# Sheet.net
KiCad netlist of a schematic drawn in Altium Designer
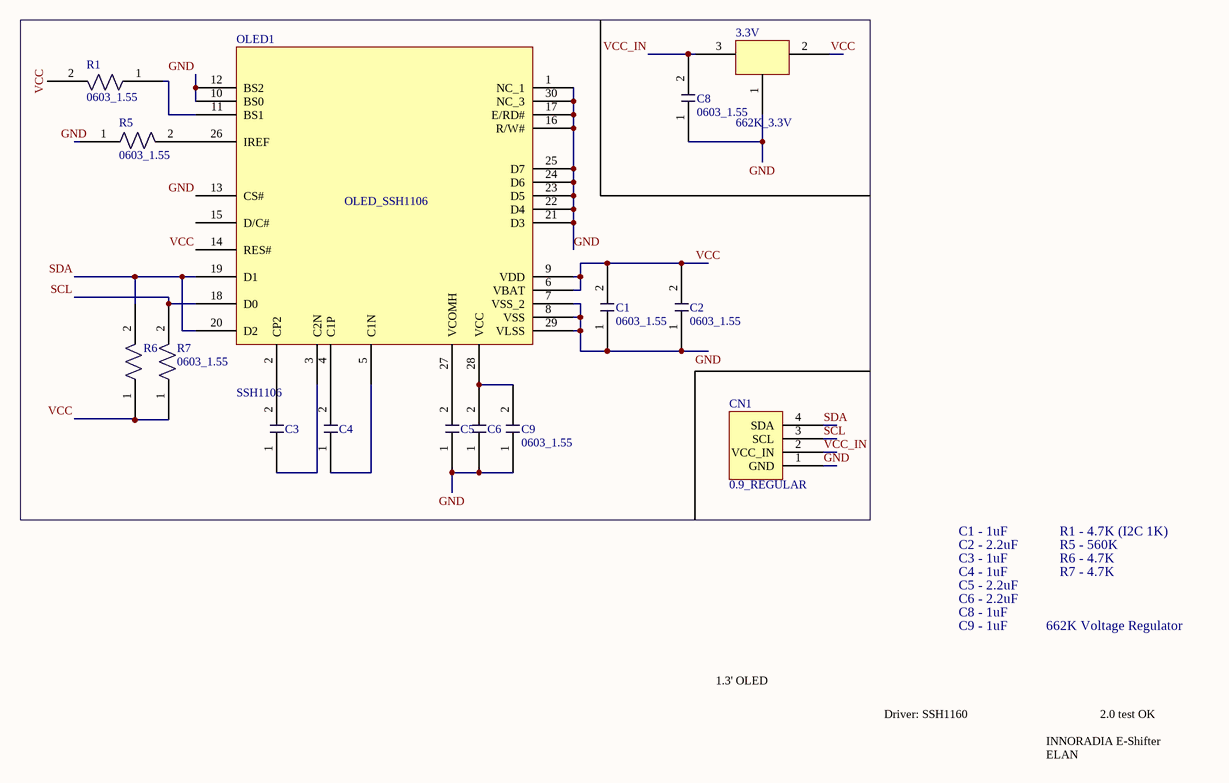
[diagram p0: Sheet.SchDoc]

(export (version "E")
  (design (tool "Eeschema 10.0.6"))
  (components
    (comp (ref "3.3V")
      (value "662K_3.3V")
      (footprint "662K_3.3V")
      (libsource (lib "Schlib") (part "662K_3.3V"))
    )
    (comp (ref "C1") (value "0603_1.55") (footprint "C_0603") (libsource (lib "Schlib") (part "C_0603")))
    (comp (ref "C2") (value "0603_1.55") (footprint "C_0603") (libsource (lib "Schlib") (part "C_0603")))
    (comp (ref "C3") (value "0603_1.55") (footprint "C_0603") (libsource (lib "Schlib") (part "C_0603")))
    (comp (ref "C4") (value "0603_1.55") (footprint "C_0603") (libsource (lib "Schlib") (part "C_0603")))
    (comp (ref "C5") (value "0603_1.55") (footprint "C_0603") (libsource (lib "Schlib") (part "C_0603")))
    (comp (ref "C6") (value "0603_1.55") (footprint "C_0603") (libsource (lib "Schlib") (part "C_0603")))
    (comp (ref "C8") (value "0603_1.55") (footprint "C_0603") (libsource (lib "Schlib") (part "C_0603")))
    (comp (ref "C9") (value "0603_1.55") (footprint "C_0603") (libsource (lib "Schlib") (part "C_0603")))
    (comp (ref "CN1")
      (value "0.9_REGULAR")
      (footprint "CONNECTOR")
      (libsource (lib "Schlib") (part "CONNECTOR"))
    )
    (comp (ref "OLED1") (value "SSH1106") (footprint "OLED_1.3") (libsource (lib "Schlib") (part "OLED_1.3")))
    (comp (ref "R1") (value "0603_1.55") (footprint "R_0603") (libsource (lib "Schlib") (part "R_0603")))
    (comp (ref "R5") (value "0603_1.55") (footprint "R_0603") (libsource (lib "Schlib") (part "R_0603")))
    (comp (ref "R6") (value "0603_1.55") (footprint "R_0603") (libsource (lib "Schlib") (part "R_0603")))
    (comp (ref "R7") (value "0603_1.55") (footprint "R_0603") (libsource (lib "Schlib") (part "R_0603")))
  )
  (nets
    (net (code "1") (name "/GND") (class "Default")
      (node (ref "3.3V") (pin "1") (pintype "passive"))
      (node (ref "C1") (pin "1") (pintype "passive"))
      (node (ref "C2") (pin "1") (pintype "passive"))
      (node (ref "C5") (pin "1") (pintype "passive"))
      (node (ref "C6") (pin "1") (pintype "passive"))
      (node (ref "C8") (pin "1") (pintype "passive"))
      (node (ref "C9") (pin "1") (pintype "passive"))
      (node (ref "CN1") (pin "1") (pinfunction "GND_1") (pintype "passive"))
      (node (ref "OLED1") (pin "1") (pinfunction "NC_1_1") (pintype "passive"))
      (node (ref "OLED1") (pin "10") (pinfunction "BS0_10") (pintype "passive"))
      (node (ref "OLED1") (pin "12") (pinfunction "BS2_12") (pintype "passive"))
      (node (ref "OLED1") (pin "13") (pinfunction "CS#_13") (pintype "passive"))
      (node (ref "OLED1") (pin "16") (pinfunction "R/W#_16") (pintype "passive"))
      (node (ref "OLED1") (pin "17") (pinfunction "E/RD#_17") (pintype "passive"))
      (node (ref "OLED1") (pin "21") (pinfunction "D3_21") (pintype "passive"))
      (node (ref "OLED1") (pin "22") (pinfunction "D4_22") (pintype "passive"))
      (node (ref "OLED1") (pin "23") (pinfunction "D5_23") (pintype "passive"))
      (node (ref "OLED1") (pin "24") (pinfunction "D6_24") (pintype "passive"))
      (node (ref "OLED1") (pin "25") (pinfunction "D7_25") (pintype "passive"))
      (node (ref "OLED1") (pin "29") (pinfunction "VLSS_29") (pintype "passive"))
      (node (ref "OLED1") (pin "30") (pinfunction "NC_3_30") (pintype "passive"))
      (node (ref "OLED1") (pin "7") (pinfunction "VSS_2_7") (pintype "passive"))
      (node (ref "OLED1") (pin "8") (pinfunction "VSS_8") (pintype "passive"))
      (node (ref "R5") (pin "1") (pintype "passive"))
    )
    (net (code "2") (name "/SCL") (class "Default")
      (node (ref "CN1") (pin "3") (pinfunction "SCL_3") (pintype "passive"))
      (node (ref "OLED1") (pin "18") (pinfunction "D0_18") (pintype "passive"))
      (node (ref "R7") (pin "2") (pintype "passive"))
    )
    (net (code "3") (name "/SDA") (class "Default")
      (node (ref "CN1") (pin "4") (pinfunction "SDA_4") (pintype "passive"))
      (node (ref "OLED1") (pin "19") (pinfunction "D1_19") (pintype "passive"))
      (node (ref "OLED1") (pin "20") (pinfunction "D2_20") (pintype "passive"))
      (node (ref "R6") (pin "2") (pintype "passive"))
    )
    (net (code "4") (name "/VCC") (class "Default")
      (node (ref "3.3V") (pin "2") (pintype "passive"))
      (node (ref "C1") (pin "2") (pintype "passive"))
      (node (ref "C2") (pin "2") (pintype "passive"))
      (node (ref "OLED1") (pin "14") (pinfunction "RES#_14") (pintype "passive"))
      (node (ref "OLED1") (pin "6") (pinfunction "VBAT_6") (pintype "passive"))
      (node (ref "OLED1") (pin "9") (pinfunction "VDD_9") (pintype "passive"))
      (node (ref "R1") (pin "2") (pintype "passive"))
      (node (ref "R6") (pin "1") (pintype "passive"))
      (node (ref "R7") (pin "1") (pintype "passive"))
    )
    (net (code "5") (name "/VCC_IN") (class "Default")
      (node (ref "3.3V") (pin "3") (pintype "passive"))
      (node (ref "C8") (pin "2") (pintype "passive"))
      (node (ref "CN1") (pin "2") (pinfunction "VCC_IN_2") (pintype "passive"))
    )
    (net (code "6") (name "Net-(OLED1-BS1)") (class "Default")
      (node (ref "OLED1") (pin "11") (pinfunction "BS1_11") (pintype "passive"))
      (node (ref "R1") (pin "1") (pintype "passive"))
    )
    (net (code "7") (name "Net-(OLED1-C1N)") (class "Default")
      (node (ref "C4") (pin "1") (pintype "passive"))
      (node (ref "OLED1") (pin "5") (pinfunction "C1N_5") (pintype "passive"))
    )
    (net (code "8") (name "Net-(OLED1-C1P)") (class "Default")
      (node (ref "C4") (pin "2") (pintype "passive"))
      (node (ref "OLED1") (pin "4") (pinfunction "C1P_4") (pintype "passive"))
    )
    (net (code "9") (name "Net-(OLED1-C2N)") (class "Default")
      (node (ref "C3") (pin "1") (pintype "passive"))
      (node (ref "OLED1") (pin "3") (pinfunction "C2N_3") (pintype "passive"))
    )
    (net (code "10") (name "Net-(OLED1-CP2)") (class "Default")
      (node (ref "C3") (pin "2") (pintype "passive"))
      (node (ref "OLED1") (pin "2") (pinfunction "CP2_2") (pintype "passive"))
    )
    (net (code "11") (name "Net-(OLED1-IREF)") (class "Default")
      (node (ref "OLED1") (pin "26") (pinfunction "IREF_26") (pintype "passive"))
      (node (ref "R5") (pin "2") (pintype "passive"))
    )
    (net (code "12") (name "Net-(OLED1-VCC)") (class "Default")
      (node (ref "C6") (pin "2") (pintype "passive"))
      (node (ref "C9") (pin "2") (pintype "passive"))
      (node (ref "OLED1") (pin "28") (pinfunction "VCC_28") (pintype "passive"))
    )
    (net (code "13") (name "Net-(OLED1-VCOMH)") (class "Default")
      (node (ref "C5") (pin "2") (pintype "passive"))
      (node (ref "OLED1") (pin "27") (pinfunction "VCOMH_27") (pintype "passive"))
    )
    (net (code "14") (name "unconnected-(OLED1-D{slash}C#-Pad15)") (class "Default")
      (node (ref "OLED1") (pin "15") (pinfunction "D/C#_15") (pintype "passive"))
    )
  )
)
